# LightLog_SMD_0_6C.net
KiCad netlist of a schematic drawn in EAGLE
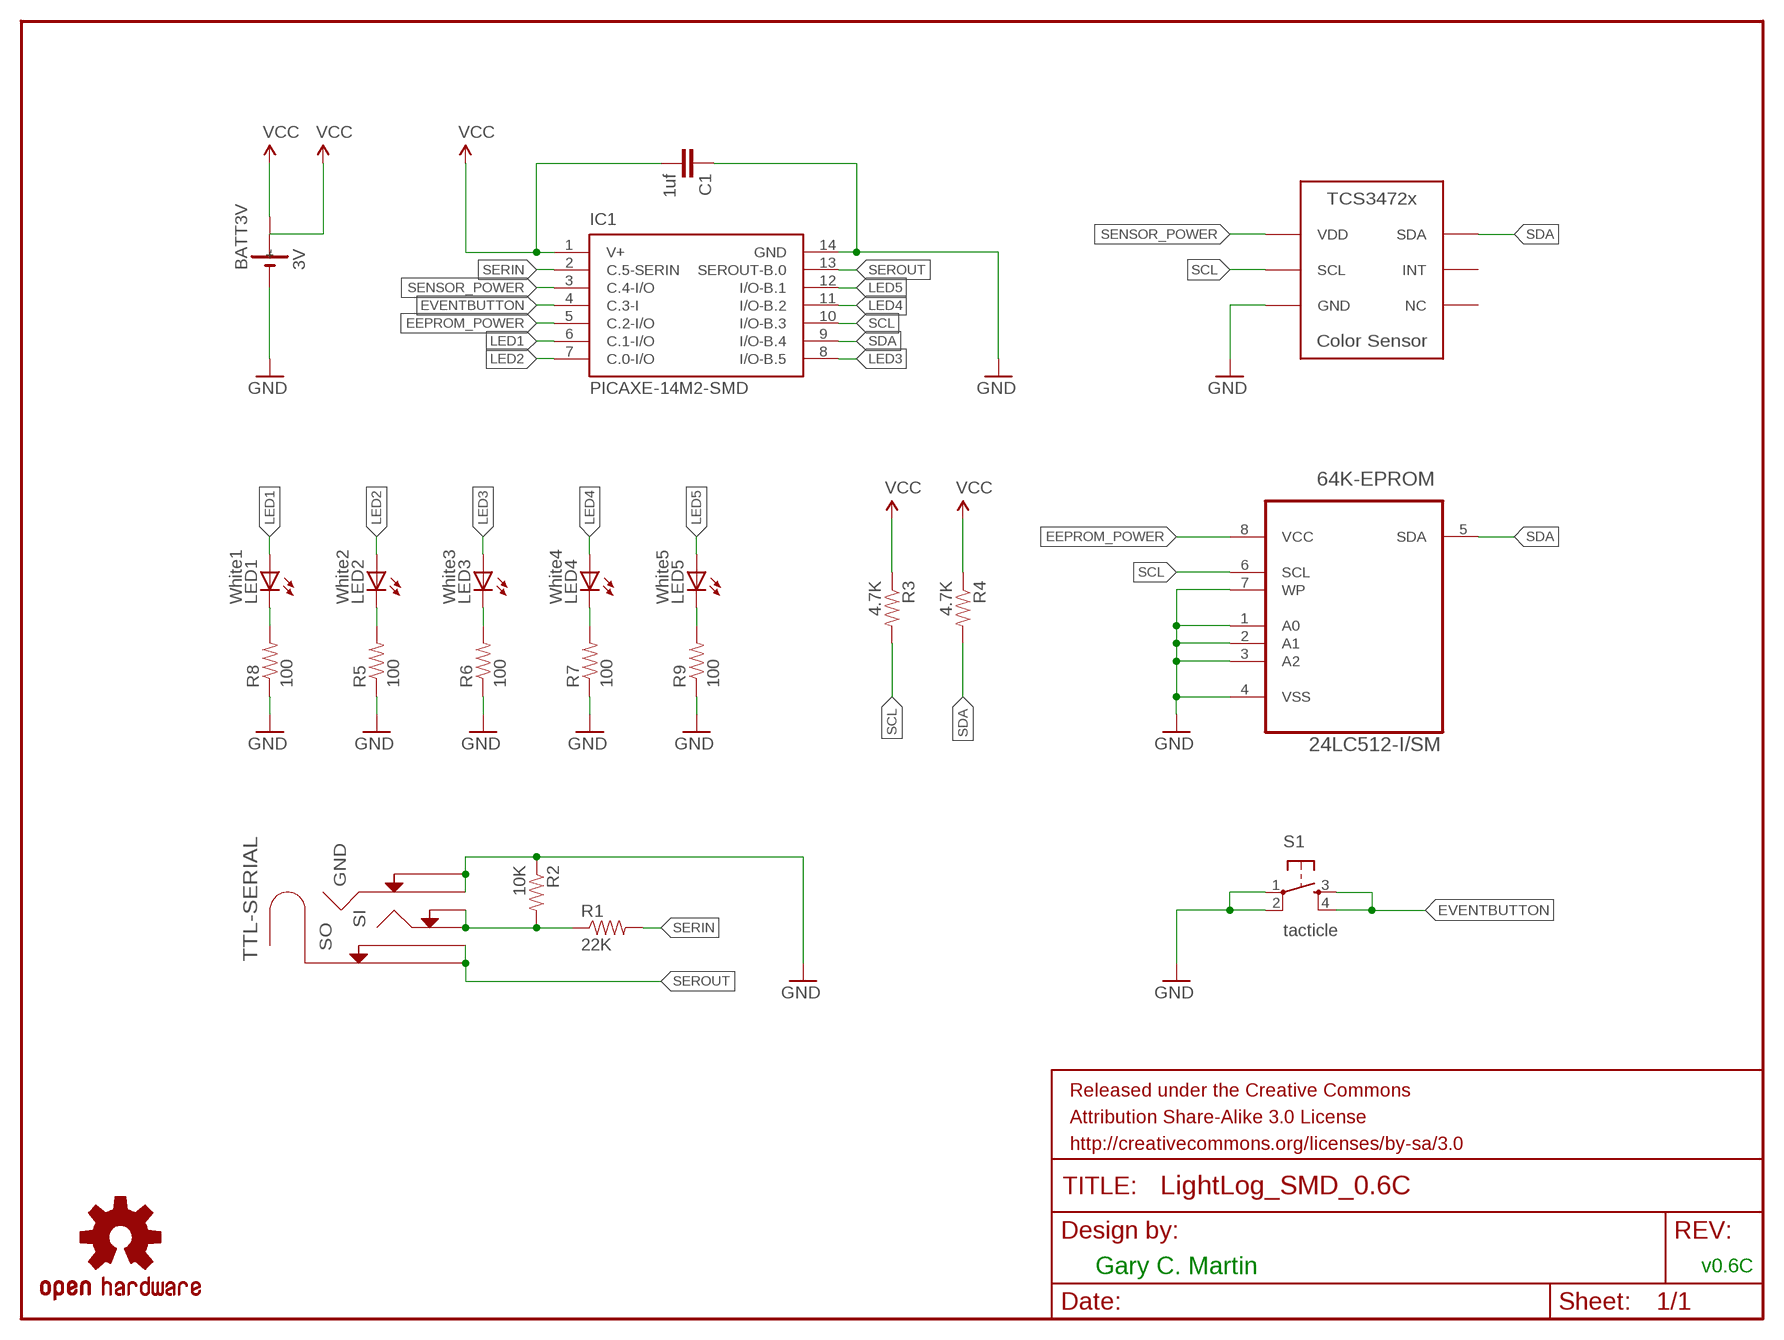
[diagram p0: schematic, sheet 1]

(export (version "E")
  (design (tool "Eeschema 10.0.6"))
  (components
    (comp (ref "64K-EPROM")
      (value "24LC512-I/SM")
      (footprint "eagle-import:SOIC127P794X203-8N")
      (libsource (lib "eagle-import") (part "24LC512-I/SM"))
    )
    (comp (ref "BATT3V")
      (value "3V")
      (footprint "eagle-import:BAT-HLD-001-CR2032-SMD")
      (libsource (lib "eagle-import") (part "BAT-HLD-001-CR2032"))
    )
    (comp (ref "C1")
      (value "1uf")
      (footprint "eagle-import:0805")
      (libsource (lib "eagle-import") (part "CAP0805"))
    )
    (comp (ref "IC1")
      (value "PICAXE-14M2-SMD")
      (footprint "eagle-import:SOIC14")
      (libsource (lib "eagle-import") (part "PICAXE-14M2-SMD"))
    )
    (comp (ref "LED1")
      (value "White1")
      (footprint "eagle-import:LED-1206")
      (libsource (lib "eagle-import") (part "LED1206"))
    )
    (comp (ref "LED2")
      (value "White2")
      (footprint "eagle-import:LED-1206")
      (libsource (lib "eagle-import") (part "LED1206"))
    )
    (comp (ref "LED3")
      (value "White3")
      (footprint "eagle-import:LED-1206")
      (libsource (lib "eagle-import") (part "LED1206"))
    )
    (comp (ref "LED4")
      (value "White4")
      (footprint "eagle-import:LED-1206")
      (libsource (lib "eagle-import") (part "LED1206"))
    )
    (comp (ref "LED5")
      (value "White5")
      (footprint "eagle-import:LED-1206")
      (libsource (lib "eagle-import") (part "LED1206"))
    )
    (comp (ref "LOGO1")
      (value "OSHW-LOGOS")
      (footprint "eagle-import:OSHW-LOGO-S")
      (libsource (lib "eagle-import") (part "OSHW-LOGOS"))
    )
    (comp (ref "R1")
      (value "22K")
      (footprint "eagle-import:0805")
      (libsource (lib "eagle-import") (part "RESISTOR0805-RES"))
    )
    (comp (ref "R2")
      (value "10K")
      (footprint "eagle-import:0805")
      (libsource (lib "eagle-import") (part "RESISTOR0805-RES"))
    )
    (comp (ref "R3")
      (value "4.7K")
      (footprint "eagle-import:0805")
      (libsource (lib "eagle-import") (part "RESISTOR0805-RES"))
    )
    (comp (ref "R4")
      (value "4.7K")
      (footprint "eagle-import:0805")
      (libsource (lib "eagle-import") (part "RESISTOR0805-RES"))
    )
    (comp (ref "R5")
      (value "100")
      (footprint "eagle-import:0805")
      (libsource (lib "eagle-import") (part "RESISTOR0805-RES"))
    )
    (comp (ref "R6")
      (value "100")
      (footprint "eagle-import:0805")
      (libsource (lib "eagle-import") (part "RESISTOR0805-RES"))
    )
    (comp (ref "R7")
      (value "100")
      (footprint "eagle-import:0805")
      (libsource (lib "eagle-import") (part "RESISTOR0805-RES"))
    )
    (comp (ref "R8")
      (value "100")
      (footprint "eagle-import:0805")
      (libsource (lib "eagle-import") (part "RESISTOR0805-RES"))
    )
    (comp (ref "R9")
      (value "100")
      (footprint "eagle-import:0805")
      (libsource (lib "eagle-import") (part "RESISTOR0805-RES"))
    )
    (comp (ref "S1")
      (value "tacticle")
      (footprint "eagle-import:TACTILE_SWITCH_SMD")
      (libsource (lib "eagle-import") (part "TAC_SWITCHSMD"))
    )
    (comp (ref "TTL-SERIAL")
      (value "3-5MM-STEREO-SOCKET")
      (footprint "eagle-import:3-5MM-SMT")
      (libsource (lib "eagle-import") (part "3-5MM-STEREO-SOCKET"))
    )
    (comp (ref "U$1")
      (value "TCS3472")
      (footprint "eagle-import:DUAL-FLAT-NO-LEAD-6PIN")
      (libsource (lib "eagle-import") (part "TCS3472"))
    )
  )
  (nets
    (net (code "1") (name "EEPROM_POWER") (class "Default")
      (node (ref "64K-EPROM") (pin "8") (pinfunction "VCC_8") (pintype "power_in"))
      (node (ref "IC1") (pin "5") (pinfunction "C.2-I/O_5") (pintype "bidirectional"))
    )
    (net (code "2") (name "EVENTBUTTON") (class "Default")
      (node (ref "IC1") (pin "4") (pinfunction "C.3-I_4") (pintype "input"))
      (node (ref "S1") (pin "3") (pinfunction "3_3") (pintype "passive"))
      (node (ref "S1") (pin "4") (pinfunction "4_4") (pintype "passive"))
    )
    (net (code "3") (name "GND") (class "Default")
      (node (ref "64K-EPROM") (pin "1") (pinfunction "A0_1") (pintype "input"))
      (node (ref "64K-EPROM") (pin "2") (pinfunction "A1_2") (pintype "input"))
      (node (ref "64K-EPROM") (pin "3") (pinfunction "A2_3") (pintype "input"))
      (node (ref "64K-EPROM") (pin "4") (pinfunction "VSS_4") (pintype "passive"))
      (node (ref "64K-EPROM") (pin "7") (pinfunction "WP_7") (pintype "input"))
      (node (ref "BATT3V") (pin "NEG") (pinfunction "-_NEG") (pintype "passive"))
      (node (ref "C1") (pin "1") (pinfunction "1_1") (pintype "passive"))
      (node (ref "IC1") (pin "14") (pinfunction "GND_14") (pintype "power_in"))
      (node (ref "R2") (pin "1") (pinfunction "1_1") (pintype "passive"))
      (node (ref "R5") (pin "1") (pinfunction "1_1") (pintype "passive"))
      (node (ref "R6") (pin "1") (pinfunction "1_1") (pintype "passive"))
      (node (ref "R7") (pin "1") (pinfunction "1_1") (pintype "passive"))
      (node (ref "R8") (pin "1") (pinfunction "1_1") (pintype "passive"))
      (node (ref "R9") (pin "1") (pinfunction "1_1") (pintype "passive"))
      (node (ref "S1") (pin "1") (pinfunction "1_1") (pintype "passive"))
      (node (ref "S1") (pin "2") (pinfunction "2_2") (pintype "passive"))
      (node (ref "TTL-SERIAL") (pin "5") (pinfunction "5_5") (pintype "bidirectional"))
      (node (ref "TTL-SERIAL") (pin "6") (pinfunction "6_6") (pintype "bidirectional"))
      (node (ref "U$1") (pin "3") (pinfunction "GND_3") (pintype "bidirectional"))
    )
    (net (code "4") (name "LED1") (class "Default")
      (node (ref "IC1") (pin "6") (pinfunction "C.1-I/O_6") (pintype "bidirectional"))
      (node (ref "LED1") (pin "A") (pinfunction "A_A") (pintype "passive"))
    )
    (net (code "5") (name "LED2") (class "Default")
      (node (ref "IC1") (pin "7") (pinfunction "C.0-I/O_7") (pintype "bidirectional"))
      (node (ref "LED2") (pin "A") (pinfunction "A_A") (pintype "passive"))
    )
    (net (code "6") (name "LED3") (class "Default")
      (node (ref "IC1") (pin "8") (pinfunction "I/O-B.5_8") (pintype "bidirectional"))
      (node (ref "LED3") (pin "A") (pinfunction "A_A") (pintype "passive"))
    )
    (net (code "7") (name "LED4") (class "Default")
      (node (ref "IC1") (pin "11") (pinfunction "I/O-B.2_11") (pintype "bidirectional"))
      (node (ref "LED4") (pin "A") (pinfunction "A_A") (pintype "passive"))
    )
    (net (code "8") (name "LED5") (class "Default")
      (node (ref "IC1") (pin "12") (pinfunction "I/O-B.1_12") (pintype "bidirectional"))
      (node (ref "LED5") (pin "A") (pinfunction "A_A") (pintype "passive"))
    )
    (net (code "9") (name "Net-(LED1-PadC)") (class "Default")
      (node (ref "LED1") (pin "C") (pinfunction "C_C") (pintype "passive"))
      (node (ref "R8") (pin "2") (pinfunction "2_2") (pintype "passive"))
    )
    (net (code "10") (name "Net-(LED2-PadC)") (class "Default")
      (node (ref "LED2") (pin "C") (pinfunction "C_C") (pintype "passive"))
      (node (ref "R5") (pin "2") (pinfunction "2_2") (pintype "passive"))
    )
    (net (code "11") (name "Net-(LED3-PadC)") (class "Default")
      (node (ref "LED3") (pin "C") (pinfunction "C_C") (pintype "passive"))
      (node (ref "R6") (pin "2") (pinfunction "2_2") (pintype "passive"))
    )
    (net (code "12") (name "Net-(LED4-PadC)") (class "Default")
      (node (ref "LED4") (pin "C") (pinfunction "C_C") (pintype "passive"))
      (node (ref "R7") (pin "2") (pinfunction "2_2") (pintype "passive"))
    )
    (net (code "13") (name "Net-(LED5-PadC)") (class "Default")
      (node (ref "LED5") (pin "C") (pinfunction "C_C") (pintype "passive"))
      (node (ref "R9") (pin "2") (pinfunction "2_2") (pintype "passive"))
    )
    (net (code "14") (name "Net-(R1-Pad1)") (class "Default")
      (node (ref "R1") (pin "1") (pinfunction "1_1") (pintype "passive"))
      (node (ref "R2") (pin "2") (pinfunction "2_2") (pintype "passive"))
      (node (ref "TTL-SERIAL") (pin "3") (pinfunction "3_3") (pintype "bidirectional"))
      (node (ref "TTL-SERIAL") (pin "4") (pinfunction "4_4") (pintype "bidirectional"))
    )
    (net (code "15") (name "SCL") (class "Default")
      (node (ref "64K-EPROM") (pin "6") (pinfunction "SCL_6") (pintype "input"))
      (node (ref "IC1") (pin "10") (pinfunction "I/O-B.3_10") (pintype "bidirectional"))
      (node (ref "R3") (pin "2") (pinfunction "2_2") (pintype "passive"))
      (node (ref "U$1") (pin "2") (pinfunction "SCL_2") (pintype "bidirectional"))
    )
    (net (code "16") (name "SDA") (class "Default")
      (node (ref "64K-EPROM") (pin "5") (pinfunction "SDA_5") (pintype "bidirectional"))
      (node (ref "IC1") (pin "9") (pinfunction "I/O-B.4_9") (pintype "bidirectional"))
      (node (ref "R4") (pin "2") (pinfunction "2_2") (pintype "passive"))
      (node (ref "U$1") (pin "6") (pinfunction "SDA_6") (pintype "bidirectional"))
    )
    (net (code "17") (name "SENSOR_POWER") (class "Default")
      (node (ref "IC1") (pin "3") (pinfunction "C.4-I/O_3") (pintype "bidirectional"))
      (node (ref "U$1") (pin "1") (pinfunction "VDD_1") (pintype "bidirectional"))
    )
    (net (code "18") (name "SERIN") (class "Default")
      (node (ref "IC1") (pin "2") (pinfunction "C.5-SERIN_2") (pintype "input"))
      (node (ref "R1") (pin "2") (pinfunction "2_2") (pintype "passive"))
    )
    (net (code "19") (name "SEROUT") (class "Default")
      (node (ref "IC1") (pin "13") (pinfunction "SEROUT-B.0_13") (pintype "output"))
      (node (ref "TTL-SERIAL") (pin "1") (pinfunction "1_1") (pintype "bidirectional"))
      (node (ref "TTL-SERIAL") (pin "2") (pinfunction "2_2") (pintype "bidirectional"))
    )
    (net (code "20") (name "VCC") (class "Default")
      (node (ref "BATT3V") (pin "POS1") (pinfunction "+_POS1") (pintype "passive"))
      (node (ref "BATT3V") (pin "POS2") (pinfunction "+_POS2") (pintype "passive"))
      (node (ref "C1") (pin "2") (pinfunction "2_2") (pintype "passive"))
      (node (ref "IC1") (pin "1") (pinfunction "V+_1") (pintype "power_in"))
      (node (ref "R3") (pin "1") (pinfunction "1_1") (pintype "passive"))
      (node (ref "R4") (pin "1") (pinfunction "1_1") (pintype "passive"))
    )
    (net (code "21") (name "unconnected-(U$1-INT-Pad5)") (class "Default")
      (node (ref "U$1") (pin "5") (pinfunction "INT_5") (pintype "bidirectional"))
    )
    (net (code "22") (name "unconnected-(U$1-NC-Pad4)") (class "Default")
      (node (ref "U$1") (pin "4") (pinfunction "NC_4") (pintype "bidirectional"))
    )
  )
)
